# ledbrick_plus_led.net
KiCad netlist of a schematic drawn in Altium Designer
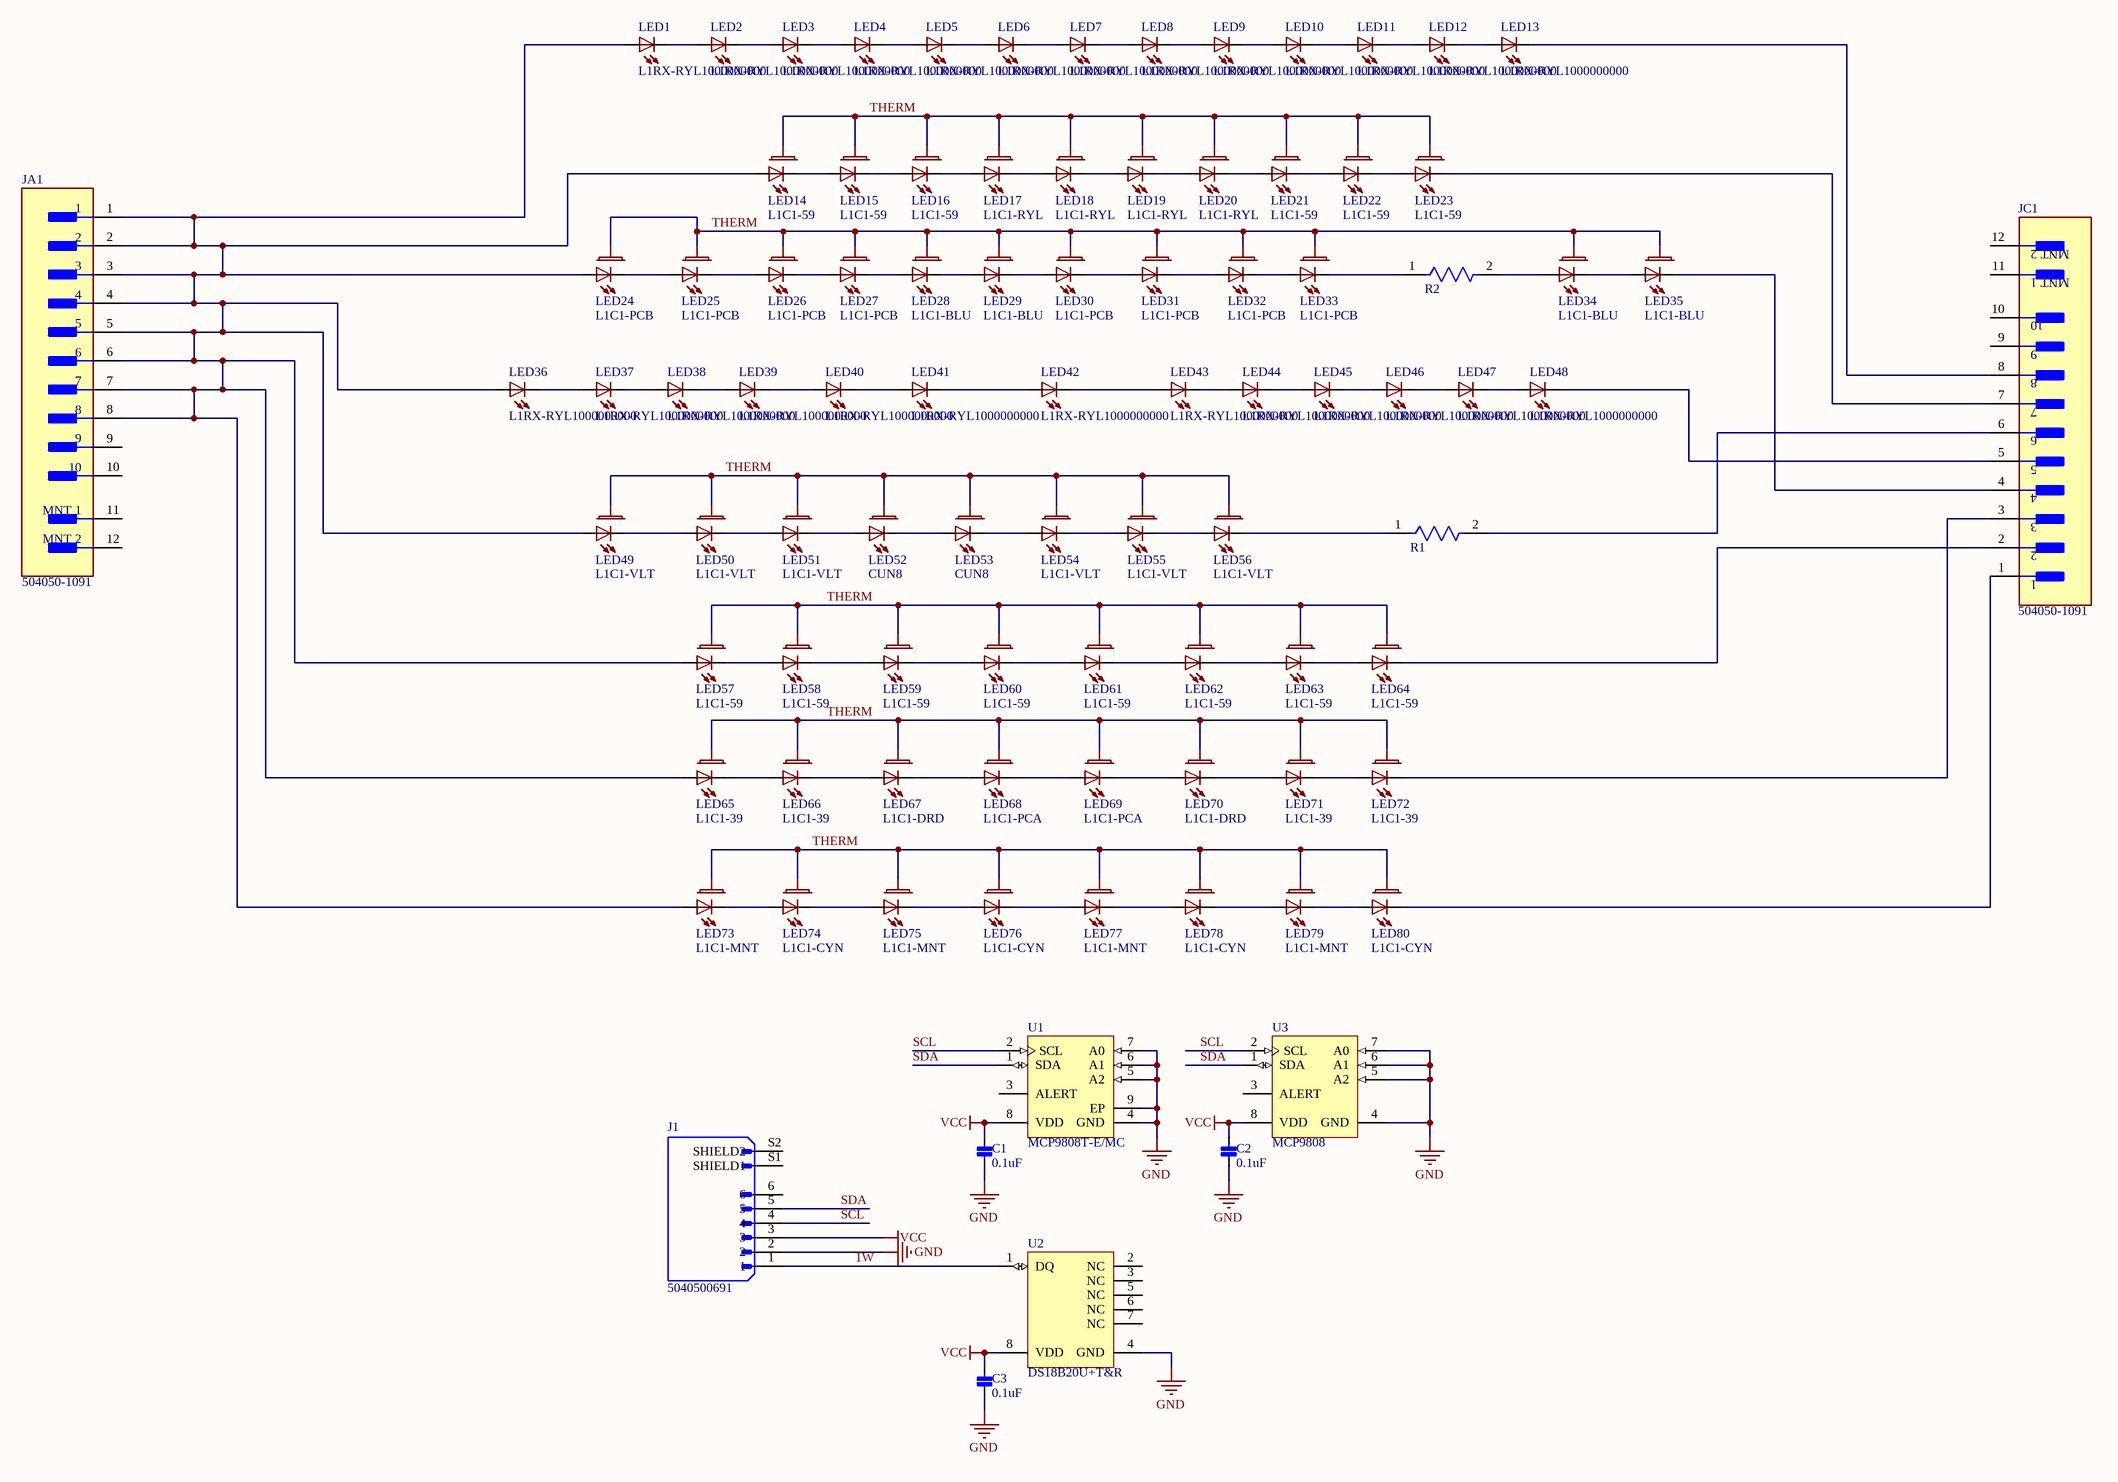
[diagram p0: ledbrick_plus_led.SchDoc]

(export (version "E")
  (design (tool "Eeschema 10.0.6"))
  (components
    (comp (ref "C1")
      (value "0.1uF")
      (footprint "FP-CL10-IPC_B")
      (description "Cap Ceramic 0.1uF 50V X7R 20% SMD 0603 125C Paper T/R")
      (fields (field (name "VOLTAGE") "50V") (field (name "Comment") "CAP 0.1uF 50V X7R 0603"))
      (libsource (lib "StackFoundry LLC") (part "C-EU"))
    )
    (comp (ref "C2")
      (value "0.1uF")
      (footprint "FP-CL10-IPC_B")
      (description "Cap Ceramic 0.1uF 50V X7R 20% SMD 0603 125C Paper T/R")
      (fields (field (name "VOLTAGE") "50V") (field (name "Comment") "CAP 0.1uF 50V X7R 0603"))
      (libsource (lib "StackFoundry LLC") (part "C-EU"))
    )
    (comp (ref "C3")
      (value "0.1uF")
      (footprint "FP-CL10-IPC_B")
      (description "Cap Ceramic 0.1uF 50V X7R 20% SMD 0603 125C Paper T/R")
      (fields (field (name "VOLTAGE") "50V") (field (name "Comment") "CAP 0.1uF 50V X7R 0603"))
      (libsource (lib "StackFoundry LLC") (part "C-EU"))
    )
    (comp (ref "J1")
      (value "5040500691")
      (footprint "MOLEX_5040500691")
      (description "CONN WIRE TO BOARD RA 6POS")
      (libsource (lib "StackFoundry LLC") (part "5040500691"))
    )
    (comp (ref "JA1")
      (value "504050-1091")
      (footprint "FP-504050-1091-MFG")
      (description "Conn Wire to Board HDR 10 POS 1.5mm Solder RA SMD Pico-Lock™ T/R")
      (libsource (lib "StackFoundry LLC") (part "6fa52caac0d1ee56d9e6a1d806c5b84"))
    )
    (comp (ref "JC1")
      (value "504050-1091")
      (footprint "FP-504050-1091-MFG")
      (description "Conn Wire to Board HDR 10 POS 1.5mm Solder RA SMD Pico-Lock™ T/R")
      (libsource (lib "") (part "6fa52caac0d1ee56d9e6a1d806c5b84_1"))
    )
    (comp (ref "LED1")
      (value "L1RX-RYL1000000000")
      (footprint "L1RX-RYL1000000000-Footprint-1")
      (description "LUXEON Rubix High Power LED Royal Blue Square Surface Mount 1635 lm 1.5 A 3.16 V")
      (libsource (lib "StackFoundry LLC") (part "L1RX-RYL"))
    )
    (comp (ref "LED2")
      (value "L1RX-RYL1000000000")
      (footprint "L1RX-RYL1000000000-Footprint-1")
      (description "LUXEON Rubix High Power LED Royal Blue Square Surface Mount 1635 lm 1.5 A 3.16 V")
      (libsource (lib "StackFoundry LLC") (part "L1RX-RYL"))
    )
    (comp (ref "LED3")
      (value "L1RX-RYL1000000000")
      (footprint "L1RX-RYL1000000000-Footprint-1")
      (description "LUXEON Rubix High Power LED Royal Blue Square Surface Mount 1635 lm 1.5 A 3.16 V")
      (libsource (lib "StackFoundry LLC") (part "L1RX-RYL"))
    )
    (comp (ref "LED4")
      (value "L1RX-RYL1000000000")
      (footprint "L1RX-RYL1000000000-Footprint-1")
      (description "LUXEON Rubix High Power LED Royal Blue Square Surface Mount 1635 lm 1.5 A 3.16 V")
      (libsource (lib "StackFoundry LLC") (part "L1RX-RYL"))
    )
    (comp (ref "LED5")
      (value "L1RX-RYL1000000000")
      (footprint "L1RX-RYL1000000000-Footprint-1")
      (description "LUXEON Rubix High Power LED Royal Blue Square Surface Mount 1635 lm 1.5 A 3.16 V")
      (libsource (lib "StackFoundry LLC") (part "L1RX-RYL"))
    )
    (comp (ref "LED6")
      (value "L1RX-RYL1000000000")
      (footprint "L1RX-RYL1000000000-Footprint-1")
      (description "LUXEON Rubix High Power LED Royal Blue Square Surface Mount 1635 lm 1.5 A 3.16 V")
      (libsource (lib "StackFoundry LLC") (part "L1RX-RYL"))
    )
    (comp (ref "LED7")
      (value "L1RX-RYL1000000000")
      (footprint "L1RX-RYL1000000000-Footprint-1")
      (description "LUXEON Rubix High Power LED Royal Blue Square Surface Mount 1635 lm 1.5 A 3.16 V")
      (libsource (lib "StackFoundry LLC") (part "L1RX-RYL"))
    )
    (comp (ref "LED8")
      (value "L1RX-RYL1000000000")
      (footprint "L1RX-RYL1000000000-Footprint-1")
      (description "LUXEON Rubix High Power LED Royal Blue Square Surface Mount 1635 lm 1.5 A 3.16 V")
      (libsource (lib "StackFoundry LLC") (part "L1RX-RYL"))
    )
    (comp (ref "LED9")
      (value "L1RX-RYL1000000000")
      (footprint "L1RX-RYL1000000000-Footprint-1")
      (description "LUXEON Rubix High Power LED Royal Blue Square Surface Mount 1635 lm 1.5 A 3.16 V")
      (libsource (lib "StackFoundry LLC") (part "L1RX-RYL"))
    )
    (comp (ref "LED10")
      (value "L1RX-RYL1000000000")
      (footprint "L1RX-RYL1000000000-Footprint-1")
      (description "LUXEON Rubix High Power LED Royal Blue Square Surface Mount 1635 lm 1.5 A 3.16 V")
      (libsource (lib "StackFoundry LLC") (part "L1RX-RYL"))
    )
    (comp (ref "LED11")
      (value "L1RX-RYL1000000000")
      (footprint "L1RX-RYL1000000000-Footprint-1")
      (description "LUXEON Rubix High Power LED Royal Blue Square Surface Mount 1635 lm 1.5 A 3.16 V")
      (libsource (lib "StackFoundry LLC") (part "L1RX-RYL"))
    )
    (comp (ref "LED12")
      (value "L1RX-RYL1000000000")
      (footprint "L1RX-RYL1000000000-Footprint-1")
      (description "LUXEON Rubix High Power LED Royal Blue Square Surface Mount 1635 lm 1.5 A 3.16 V")
      (libsource (lib "StackFoundry LLC") (part "L1RX-RYL"))
    )
    (comp (ref "LED13")
      (value "L1RX-RYL1000000000")
      (footprint "L1RX-RYL1000000000-Footprint-1")
      (description "LUXEON Rubix High Power LED Royal Blue Square Surface Mount 1635 lm 1.5 A 3.16 V")
      (libsource (lib "StackFoundry LLC") (part "L1RX-RYL"))
    )
    (comp (ref "LED14")
      (value "L1C1-59")
      (footprint "LUXEON_C_DATASHEET")
      (libsource (lib "StackFoundry LLC") (part "LED_THERMAL"))
    )
    (comp (ref "LED15")
      (value "L1C1-59")
      (footprint "LUXEON_C_DATASHEET")
      (libsource (lib "StackFoundry LLC") (part "LED_THERMAL"))
    )
    (comp (ref "LED16")
      (value "L1C1-59")
      (footprint "LUXEON_C_DATASHEET")
      (libsource (lib "StackFoundry LLC") (part "LED_THERMAL"))
    )
    (comp (ref "LED17")
      (value "L1C1-RYL")
      (footprint "LUXEON_C_DATASHEET")
      (libsource (lib "StackFoundry LLC") (part "LED_THERMAL"))
    )
    (comp (ref "LED18")
      (value "L1C1-RYL")
      (footprint "LUXEON_C_DATASHEET")
      (libsource (lib "StackFoundry LLC") (part "LED_THERMAL"))
    )
    (comp (ref "LED19")
      (value "L1C1-RYL")
      (footprint "LUXEON_C_DATASHEET")
      (libsource (lib "StackFoundry LLC") (part "LED_THERMAL"))
    )
    (comp (ref "LED20")
      (value "L1C1-RYL")
      (footprint "LUXEON_C_DATASHEET")
      (libsource (lib "StackFoundry LLC") (part "LED_THERMAL"))
    )
    (comp (ref "LED21")
      (value "L1C1-59")
      (footprint "LUXEON_C_DATASHEET")
      (libsource (lib "StackFoundry LLC") (part "LED_THERMAL"))
    )
    (comp (ref "LED22")
      (value "L1C1-59")
      (footprint "LUXEON_C_DATASHEET")
      (libsource (lib "StackFoundry LLC") (part "LED_THERMAL"))
    )
    (comp (ref "LED23")
      (value "L1C1-59")
      (footprint "LUXEON_C_DATASHEET")
      (libsource (lib "StackFoundry LLC") (part "LED_THERMAL"))
    )
    (comp (ref "LED24")
      (value "L1C1-PCB")
      (footprint "LUXEON_C_DATASHEET")
      (libsource (lib "StackFoundry LLC") (part "LED_THERMAL"))
    )
    (comp (ref "LED25")
      (value "L1C1-PCB")
      (footprint "LUXEON_C_DATASHEET")
      (libsource (lib "StackFoundry LLC") (part "LED_THERMAL"))
    )
    (comp (ref "LED26")
      (value "L1C1-PCB")
      (footprint "LUXEON_C_DATASHEET")
      (libsource (lib "StackFoundry LLC") (part "LED_THERMAL"))
    )
    (comp (ref "LED27")
      (value "L1C1-PCB")
      (footprint "LUXEON_C_DATASHEET")
      (libsource (lib "StackFoundry LLC") (part "LED_THERMAL"))
    )
    (comp (ref "LED28")
      (value "L1C1-BLU")
      (footprint "LUXEON_C_DATASHEET")
      (libsource (lib "StackFoundry LLC") (part "LED_THERMAL"))
    )
    (comp (ref "LED29")
      (value "L1C1-BLU")
      (footprint "LUXEON_C_DATASHEET")
      (libsource (lib "StackFoundry LLC") (part "LED_THERMAL"))
    )
    (comp (ref "LED30")
      (value "L1C1-PCB")
      (footprint "LUXEON_C_DATASHEET")
      (libsource (lib "StackFoundry LLC") (part "LED_THERMAL"))
    )
    (comp (ref "LED31")
      (value "L1C1-PCB")
      (footprint "LUXEON_C_DATASHEET")
      (libsource (lib "StackFoundry LLC") (part "LED_THERMAL"))
    )
    (comp (ref "LED32")
      (value "L1C1-PCB")
      (footprint "LUXEON_C_DATASHEET")
      (libsource (lib "StackFoundry LLC") (part "LED_THERMAL"))
    )
    (comp (ref "LED33")
      (value "L1C1-PCB")
      (footprint "LUXEON_C_DATASHEET")
      (libsource (lib "StackFoundry LLC") (part "LED_THERMAL"))
    )
    (comp (ref "LED34")
      (value "L1C1-BLU")
      (footprint "LUXEON_C_DATASHEET")
      (libsource (lib "StackFoundry LLC") (part "LED_THERMAL"))
    )
    (comp (ref "LED35")
      (value "L1C1-BLU")
      (footprint "LUXEON_C_DATASHEET")
      (libsource (lib "StackFoundry LLC") (part "LED_THERMAL"))
    )
    (comp (ref "LED36")
      (value "L1RX-RYL1000000000")
      (footprint "L1RX-RYL1000000000-Footprint-1")
      (description "LUXEON Rubix High Power LED Royal Blue Square Surface Mount 1635 lm 1.5 A 3.16 V")
      (libsource (lib "StackFoundry LLC") (part "L1RX-RYL"))
    )
    (comp (ref "LED37")
      (value "L1RX-RYL1000000000")
      (footprint "L1RX-RYL1000000000-Footprint-1")
      (description "LUXEON Rubix High Power LED Royal Blue Square Surface Mount 1635 lm 1.5 A 3.16 V")
      (libsource (lib "StackFoundry LLC") (part "L1RX-RYL"))
    )
    (comp (ref "LED38")
      (value "L1RX-RYL1000000000")
      (footprint "L1RX-RYL1000000000-Footprint-1")
      (description "LUXEON Rubix High Power LED Royal Blue Square Surface Mount 1635 lm 1.5 A 3.16 V")
      (libsource (lib "StackFoundry LLC") (part "L1RX-RYL"))
    )
    (comp (ref "LED39")
      (value "L1RX-RYL1000000000")
      (footprint "L1RX-RYL1000000000-Footprint-1")
      (description "LUXEON Rubix High Power LED Royal Blue Square Surface Mount 1635 lm 1.5 A 3.16 V")
      (libsource (lib "StackFoundry LLC") (part "L1RX-RYL"))
    )
    (comp (ref "LED40")
      (value "L1RX-RYL1000000000")
      (footprint "L1RX-RYL1000000000-Footprint-1")
      (description "LUXEON Rubix High Power LED Royal Blue Square Surface Mount 1635 lm 1.5 A 3.16 V")
      (libsource (lib "StackFoundry LLC") (part "L1RX-RYL"))
    )
    (comp (ref "LED41")
      (value "L1RX-RYL1000000000")
      (footprint "L1RX-RYL1000000000-Footprint-1")
      (description "LUXEON Rubix High Power LED Royal Blue Square Surface Mount 1635 lm 1.5 A 3.16 V")
      (libsource (lib "StackFoundry LLC") (part "L1RX-RYL"))
    )
    (comp (ref "LED42")
      (value "L1RX-RYL1000000000")
      (footprint "L1RX-RYL1000000000-Footprint-1")
      (description "LUXEON Rubix High Power LED Royal Blue Square Surface Mount 1635 lm 1.5 A 3.16 V")
      (libsource (lib "StackFoundry LLC") (part "L1RX-RYL"))
    )
    (comp (ref "LED43")
      (value "L1RX-RYL1000000000")
      (footprint "L1RX-RYL1000000000-Footprint-1")
      (description "LUXEON Rubix High Power LED Royal Blue Square Surface Mount 1635 lm 1.5 A 3.16 V")
      (libsource (lib "StackFoundry LLC") (part "L1RX-RYL"))
    )
    (comp (ref "LED44")
      (value "L1RX-RYL1000000000")
      (footprint "L1RX-RYL1000000000-Footprint-1")
      (description "LUXEON Rubix High Power LED Royal Blue Square Surface Mount 1635 lm 1.5 A 3.16 V")
      (libsource (lib "StackFoundry LLC") (part "L1RX-RYL"))
    )
    (comp (ref "LED45")
      (value "L1RX-RYL1000000000")
      (footprint "L1RX-RYL1000000000-Footprint-1")
      (description "LUXEON Rubix High Power LED Royal Blue Square Surface Mount 1635 lm 1.5 A 3.16 V")
      (libsource (lib "StackFoundry LLC") (part "L1RX-RYL"))
    )
    (comp (ref "LED46")
      (value "L1RX-RYL1000000000")
      (footprint "L1RX-RYL1000000000-Footprint-1")
      (description "LUXEON Rubix High Power LED Royal Blue Square Surface Mount 1635 lm 1.5 A 3.16 V")
      (libsource (lib "StackFoundry LLC") (part "L1RX-RYL"))
    )
    (comp (ref "LED47")
      (value "L1RX-RYL1000000000")
      (footprint "L1RX-RYL1000000000-Footprint-1")
      (description "LUXEON Rubix High Power LED Royal Blue Square Surface Mount 1635 lm 1.5 A 3.16 V")
      (libsource (lib "StackFoundry LLC") (part "L1RX-RYL"))
    )
    (comp (ref "LED48")
      (value "L1RX-RYL1000000000")
      (footprint "L1RX-RYL1000000000-Footprint-1")
      (description "LUXEON Rubix High Power LED Royal Blue Square Surface Mount 1635 lm 1.5 A 3.16 V")
      (libsource (lib "StackFoundry LLC") (part "L1RX-RYL"))
    )
    (comp (ref "LED49")
      (value "L1C1-VLT")
      (footprint "LUXEON_C_DATASHEET")
      (libsource (lib "StackFoundry LLC") (part "LED_THERMAL"))
    )
    (comp (ref "LED50")
      (value "L1C1-VLT")
      (footprint "LUXEON_C_DATASHEET")
      (libsource (lib "StackFoundry LLC") (part "LED_THERMAL"))
    )
    (comp (ref "LED51")
      (value "L1C1-VLT")
      (footprint "LUXEON_C_DATASHEET")
      (libsource (lib "StackFoundry LLC") (part "LED_THERMAL"))
    )
    (comp (ref "LED52")
      (value "CUN8")
      (footprint "VIOSYS_Z5")
      (libsource (lib "StackFoundry LLC") (part "LED_THERMAL"))
    )
    (comp (ref "LED53")
      (value "CUN8")
      (footprint "VIOSYS_Z5")
      (libsource (lib "StackFoundry LLC") (part "LED_THERMAL"))
    )
    (comp (ref "LED54")
      (value "L1C1-VLT")
      (footprint "LUXEON_C_DATASHEET")
      (libsource (lib "StackFoundry LLC") (part "LED_THERMAL"))
    )
    (comp (ref "LED55")
      (value "L1C1-VLT")
      (footprint "LUXEON_C_DATASHEET")
      (libsource (lib "StackFoundry LLC") (part "LED_THERMAL"))
    )
    (comp (ref "LED56")
      (value "L1C1-VLT")
      (footprint "LUXEON_C_DATASHEET")
      (libsource (lib "StackFoundry LLC") (part "LED_THERMAL"))
    )
    (comp (ref "LED57")
      (value "L1C1-59")
      (footprint "LUXEON_C_DATASHEET")
      (libsource (lib "StackFoundry LLC") (part "LED_THERMAL"))
    )
    (comp (ref "LED58")
      (value "L1C1-59")
      (footprint "LUXEON_C_DATASHEET")
      (libsource (lib "StackFoundry LLC") (part "LED_THERMAL"))
    )
    (comp (ref "LED59")
      (value "L1C1-59")
      (footprint "LUXEON_C_DATASHEET")
      (libsource (lib "StackFoundry LLC") (part "LED_THERMAL"))
    )
    (comp (ref "LED60")
      (value "L1C1-59")
      (footprint "LUXEON_C_DATASHEET")
      (libsource (lib "StackFoundry LLC") (part "LED_THERMAL"))
    )
    (comp (ref "LED61")
      (value "L1C1-59")
      (footprint "LUXEON_C_DATASHEET")
      (libsource (lib "StackFoundry LLC") (part "LED_THERMAL"))
    )
    (comp (ref "LED62")
      (value "L1C1-59")
      (footprint "LUXEON_C_DATASHEET")
      (libsource (lib "StackFoundry LLC") (part "LED_THERMAL"))
    )
    (comp (ref "LED63")
      (value "L1C1-59")
      (footprint "LUXEON_C_DATASHEET")
      (libsource (lib "StackFoundry LLC") (part "LED_THERMAL"))
    )
    (comp (ref "LED64")
      (value "L1C1-59")
      (footprint "LUXEON_C_DATASHEET")
      (libsource (lib "StackFoundry LLC") (part "LED_THERMAL"))
    )
    (comp (ref "LED65")
      (value "L1C1-39")
      (footprint "LUXEON_C_DATASHEET")
      (libsource (lib "StackFoundry LLC") (part "LED_THERMAL"))
    )
    (comp (ref "LED66")
      (value "L1C1-39")
      (footprint "LUXEON_C_DATASHEET")
      (libsource (lib "StackFoundry LLC") (part "LED_THERMAL"))
    )
    (comp (ref "LED67")
      (value "L1C1-DRD")
      (footprint "LUXEON_C_DATASHEET")
      (libsource (lib "StackFoundry LLC") (part "LED_THERMAL"))
    )
    (comp (ref "LED68")
      (value "L1C1-PCA")
      (footprint "LUXEON_C_DATASHEET")
      (libsource (lib "StackFoundry LLC") (part "LED_THERMAL"))
    )
    (comp (ref "LED69")
      (value "L1C1-PCA")
      (footprint "LUXEON_C_DATASHEET")
      (libsource (lib "StackFoundry LLC") (part "LED_THERMAL"))
    )
    (comp (ref "LED70")
      (value "L1C1-DRD")
      (footprint "LUXEON_C_DATASHEET")
      (libsource (lib "StackFoundry LLC") (part "LED_THERMAL"))
    )
    (comp (ref "LED71")
      (value "L1C1-39")
      (footprint "LUXEON_C_DATASHEET")
      (libsource (lib "StackFoundry LLC") (part "LED_THERMAL"))
    )
    (comp (ref "LED72")
      (value "L1C1-39")
      (footprint "LUXEON_C_DATASHEET")
      (libsource (lib "StackFoundry LLC") (part "LED_THERMAL"))
    )
    (comp (ref "LED73")
      (value "L1C1-MNT")
      (footprint "LUXEON_C_DATASHEET")
      (libsource (lib "StackFoundry LLC") (part "LED_THERMAL"))
    )
    (comp (ref "LED74")
      (value "L1C1-CYN")
      (footprint "LUXEON_C_DATASHEET")
      (libsource (lib "StackFoundry LLC") (part "LED_THERMAL"))
    )
    (comp (ref "LED75")
      (value "L1C1-MNT")
      (footprint "LUXEON_C_DATASHEET")
      (libsource (lib "StackFoundry LLC") (part "LED_THERMAL"))
    )
    (comp (ref "LED76")
      (value "L1C1-CYN")
      (footprint "LUXEON_C_DATASHEET")
      (libsource (lib "StackFoundry LLC") (part "LED_THERMAL"))
    )
    (comp (ref "LED77")
      (value "L1C1-MNT")
      (footprint "LUXEON_C_DATASHEET")
      (libsource (lib "StackFoundry LLC") (part "LED_THERMAL"))
    )
    (comp (ref "LED78")
      (value "L1C1-CYN")
      (footprint "LUXEON_C_DATASHEET")
      (libsource (lib "StackFoundry LLC") (part "LED_THERMAL"))
    )
    (comp (ref "LED79")
      (value "L1C1-MNT")
      (footprint "LUXEON_C_DATASHEET")
      (libsource (lib "StackFoundry LLC") (part "LED_THERMAL"))
    )
    (comp (ref "LED80")
      (value "L1C1-CYN")
      (footprint "LUXEON_C_DATASHEET")
      (libsource (lib "StackFoundry LLC") (part "LED_THERMAL"))
    )
    (comp (ref "R1")
      (value "0R 1206")
      (footprint "FP-RC1206-IPC_B")
      (description "Res Jumper Thick Film 1206 0 Ohm 5% 1/4W Molded SMD Paper T/R")
      (fields (field (name "TOLERANCE") "5%"))
      (libsource (lib "StackFoundry LLC") (part "1029c3af85768c4190bb7ad29bc67b5"))
    )
    (comp (ref "R2")
      (value "0R 1206")
      (footprint "FP-RC1206-IPC_B")
      (description "Res Jumper Thick Film 1206 0 Ohm 5% 1/4W Molded SMD Paper T/R")
      (fields (field (name "TOLERANCE") "5%"))
      (libsource (lib "StackFoundry LLC") (part "1029c3af85768c4190bb7ad29bc67b5"))
    )
    (comp (ref "U1")
      (value "MCP9808T-E/MC")
      (footprint "MCHP-DFN-MC8_V")
      (description "Temp Sensor Digital Serial (2-Wire, I2C) 8-Pin DFN EP T/R")
      (libsource (lib "StackFoundry LLC") (part "MCHP-MCP9808-DFN-8"))
    )
    (comp (ref "U2")
      (value "DS18B20U+T&R")
      (footprint "MAXM-U8+1_N")
      (description "Temp Sensor Digital Serial (1-Wire) 8-Pin uMAX T/R")
      (libsource (lib "StackFoundry LLC") (part "DS18B20-U8"))
    )
    (comp (ref "U3")
      (value "MCP9808")
      (footprint "MCHP-MSOP-MS8_M")
      (description "Temp Sensor Digital Serial (2-Wire, I2C) 8-Pin MSOP Tube")
      (libsource (lib "StackFoundry LLC") (part "MCHP-MCP9808-MSOP-8"))
    )
  )
  (nets
    (net (code "1") (name "/1W") (class "Default")
      (node (ref "J1") (pin "1") (pinfunction "1_1") (pintype "passive"))
      (node (ref "U2") (pin "1") (pinfunction "DQ_1") (pintype "bidirectional"))
    )
    (net (code "2") (name "/SCL") (class "Default")
      (node (ref "J1") (pin "4") (pinfunction "4_4") (pintype "passive"))
      (node (ref "U1") (pin "2") (pinfunction "SCL_2") (pintype "input"))
      (node (ref "U3") (pin "2") (pinfunction "SCL_2") (pintype "input"))
    )
    (net (code "3") (name "/SDA") (class "Default")
      (node (ref "J1") (pin "5") (pinfunction "5_5") (pintype "passive"))
      (node (ref "U1") (pin "1") (pinfunction "SDA_1") (pintype "bidirectional"))
      (node (ref "U3") (pin "1") (pinfunction "SDA_1") (pintype "bidirectional"))
    )
    (net (code "4") (name "/THERM") (class "Default")
      (node (ref "LED14") (pin "PAD") (pinfunction "PAD_PAD") (pintype "passive"))
      (node (ref "LED15") (pin "PAD") (pinfunction "PAD_PAD") (pintype "passive"))
      (node (ref "LED16") (pin "PAD") (pinfunction "PAD_PAD") (pintype "passive"))
      (node (ref "LED17") (pin "PAD") (pinfunction "PAD_PAD") (pintype "passive"))
      (node (ref "LED18") (pin "PAD") (pinfunction "PAD_PAD") (pintype "passive"))
      (node (ref "LED19") (pin "PAD") (pinfunction "PAD_PAD") (pintype "passive"))
      (node (ref "LED20") (pin "PAD") (pinfunction "PAD_PAD") (pintype "passive"))
      (node (ref "LED21") (pin "PAD") (pinfunction "PAD_PAD") (pintype "passive"))
      (node (ref "LED22") (pin "PAD") (pinfunction "PAD_PAD") (pintype "passive"))
      (node (ref "LED23") (pin "PAD") (pinfunction "PAD_PAD") (pintype "passive"))
      (node (ref "LED24") (pin "PAD") (pinfunction "PAD_PAD") (pintype "passive"))
      (node (ref "LED25") (pin "PAD") (pinfunction "PAD_PAD") (pintype "passive"))
      (node (ref "LED26") (pin "PAD") (pinfunction "PAD_PAD") (pintype "passive"))
      (node (ref "LED27") (pin "PAD") (pinfunction "PAD_PAD") (pintype "passive"))
      (node (ref "LED28") (pin "PAD") (pinfunction "PAD_PAD") (pintype "passive"))
      (node (ref "LED29") (pin "PAD") (pinfunction "PAD_PAD") (pintype "passive"))
      (node (ref "LED30") (pin "PAD") (pinfunction "PAD_PAD") (pintype "passive"))
      (node (ref "LED31") (pin "PAD") (pinfunction "PAD_PAD") (pintype "passive"))
      (node (ref "LED32") (pin "PAD") (pinfunction "PAD_PAD") (pintype "passive"))
      (node (ref "LED33") (pin "PAD") (pinfunction "PAD_PAD") (pintype "passive"))
      (node (ref "LED34") (pin "PAD") (pinfunction "PAD_PAD") (pintype "passive"))
      (node (ref "LED35") (pin "PAD") (pinfunction "PAD_PAD") (pintype "passive"))
      (node (ref "LED49") (pin "PAD") (pinfunction "PAD_PAD") (pintype "passive"))
      (node (ref "LED50") (pin "PAD") (pinfunction "PAD_PAD") (pintype "passive"))
      (node (ref "LED51") (pin "PAD") (pinfunction "PAD_PAD") (pintype "passive"))
      (node (ref "LED52") (pin "PAD") (pinfunction "PAD_PAD") (pintype "passive"))
      (node (ref "LED53") (pin "PAD") (pinfunction "PAD_PAD") (pintype "passive"))
      (node (ref "LED54") (pin "PAD") (pinfunction "PAD_PAD") (pintype "passive"))
      (node (ref "LED55") (pin "PAD") (pinfunction "PAD_PAD") (pintype "passive"))
      (node (ref "LED56") (pin "PAD") (pinfunction "PAD_PAD") (pintype "passive"))
      (node (ref "LED57") (pin "PAD") (pinfunction "PAD_PAD") (pintype "passive"))
      (node (ref "LED58") (pin "PAD") (pinfunction "PAD_PAD") (pintype "passive"))
      (node (ref "LED59") (pin "PAD") (pinfunction "PAD_PAD") (pintype "passive"))
      (node (ref "LED60") (pin "PAD") (pinfunction "PAD_PAD") (pintype "passive"))
      (node (ref "LED61") (pin "PAD") (pinfunction "PAD_PAD") (pintype "passive"))
      (node (ref "LED62") (pin "PAD") (pinfunction "PAD_PAD") (pintype "passive"))
      (node (ref "LED63") (pin "PAD") (pinfunction "PAD_PAD") (pintype "passive"))
      (node (ref "LED64") (pin "PAD") (pinfunction "PAD_PAD") (pintype "passive"))
      (node (ref "LED65") (pin "PAD") (pinfunction "PAD_PAD") (pintype "passive"))
      (node (ref "LED66") (pin "PAD") (pinfunction "PAD_PAD") (pintype "passive"))
      (node (ref "LED67") (pin "PAD") (pinfunction "PAD_PAD") (pintype "passive"))
      (node (ref "LED68") (pin "PAD") (pinfunction "PAD_PAD") (pintype "passive"))
      (node (ref "LED69") (pin "PAD") (pinfunction "PAD_PAD") (pintype "passive"))
      (node (ref "LED70") (pin "PAD") (pinfunction "PAD_PAD") (pintype "passive"))
      (node (ref "LED71") (pin "PAD") (pinfunction "PAD_PAD") (pintype "passive"))
      (node (ref "LED72") (pin "PAD") (pinfunction "PAD_PAD") (pintype "passive"))
      (node (ref "LED73") (pin "PAD") (pinfunction "PAD_PAD") (pintype "passive"))
      (node (ref "LED74") (pin "PAD") (pinfunction "PAD_PAD") (pintype "passive"))
      (node (ref "LED75") (pin "PAD") (pinfunction "PAD_PAD") (pintype "passive"))
      (node (ref "LED76") (pin "PAD") (pinfunction "PAD_PAD") (pintype "passive"))
      (node (ref "LED77") (pin "PAD") (pinfunction "PAD_PAD") (pintype "passive"))
      (node (ref "LED78") (pin "PAD") (pinfunction "PAD_PAD") (pintype "passive"))
      (node (ref "LED79") (pin "PAD") (pinfunction "PAD_PAD") (pintype "passive"))
      (node (ref "LED80") (pin "PAD") (pinfunction "PAD_PAD") (pintype "passive"))
    )
    (net (code "5") (name "GND") (class "Default")
      (node (ref "C1") (pin "2") (pinfunction "2_2") (pintype "passive"))
      (node (ref "C2") (pin "2") (pinfunction "2_2") (pintype "passive"))
      (node (ref "C3") (pin "2") (pinfunction "2_2") (pintype "passive"))
      (node (ref "J1") (pin "2") (pinfunction "2_2") (pintype "passive"))
      (node (ref "U1") (pin "4") (pinfunction "GND_4") (pintype "power_in"))
      (node (ref "U1") (pin "5") (pinfunction "A2_5") (pintype "input"))
      (node (ref "U1") (pin "6") (pinfunction "A1_6") (pintype "input"))
      (node (ref "U1") (pin "7") (pinfunction "A0_7") (pintype "input"))
      (node (ref "U1") (pin "9") (pinfunction "EP_9") (pintype "power_in"))
      (node (ref "U2") (pin "4") (pinfunction "GND_4") (pintype "power_in"))
      (node (ref "U3") (pin "4") (pinfunction "GND_4") (pintype "power_in"))
      (node (ref "U3") (pin "5") (pinfunction "A2_5") (pintype "input"))
      (node (ref "U3") (pin "6") (pinfunction "A1_6") (pintype "input"))
      (node (ref "U3") (pin "7") (pinfunction "A0_7") (pintype "input"))
    )
    (net (code "6") (name "Net-(JA1-Pad1)") (class "Default")
      (node (ref "JA1") (pin "1") (pinfunction "1_1") (pintype "passive"))
      (node (ref "JA1") (pin "2") (pinfunction "2_2") (pintype "passive"))
      (node (ref "JA1") (pin "3") (pinfunction "3_3") (pintype "passive"))
      (node (ref "JA1") (pin "4") (pinfunction "4_4") (pintype "passive"))
      (node (ref "JA1") (pin "5") (pinfunction "5_5") (pintype "passive"))
      (node (ref "JA1") (pin "6") (pinfunction "6_6") (pintype "passive"))
      (node (ref "JA1") (pin "7") (pinfunction "7_7") (pintype "passive"))
      (node (ref "JA1") (pin "8") (pinfunction "8_8") (pintype "passive"))
      (node (ref "LED1") (pin "A") (pinfunction "A_A") (pintype "passive"))
      (node (ref "LED14") (pin "A") (pinfunction "A_A") (pintype "passive"))
      (node (ref "LED24") (pin "A") (pinfunction "A_A") (pintype "passive"))
      (node (ref "LED36") (pin "A") (pinfunction "A_A") (pintype "passive"))
      (node (ref "LED49") (pin "A") (pinfunction "A_A") (pintype "passive"))
      (node (ref "LED57") (pin "A") (pinfunction "A_A") (pintype "passive"))
      (node (ref "LED65") (pin "A") (pinfunction "A_A") (pintype "passive"))
      (node (ref "LED73") (pin "A") (pinfunction "A_A") (pintype "passive"))
    )
    (net (code "7") (name "Net-(JC1-Pad1)") (class "Default")
      (node (ref "JC1") (pin "1") (pinfunction "1_1") (pintype "passive"))
      (node (ref "LED80") (pin "C") (pinfunction "C_C") (pintype "passive"))
    )
    (net (code "8") (name "Net-(JC1-Pad2)") (class "Default")
      (node (ref "JC1") (pin "2") (pinfunction "2_2") (pintype "passive"))
      (node (ref "LED64") (pin "C") (pinfunction "C_C") (pintype "passive"))
    )
    (net (code "9") (name "Net-(JC1-Pad3)") (class "Default")
      (node (ref "JC1") (pin "3") (pinfunction "3_3") (pintype "passive"))
      (node (ref "LED72") (pin "C") (pinfunction "C_C") (pintype "passive"))
    )
    (net (code "10") (name "Net-(JC1-Pad4)") (class "Default")
      (node (ref "JC1") (pin "4") (pinfunction "4_4") (pintype "passive"))
      (node (ref "LED35") (pin "C") (pinfunction "C_C") (pintype "passive"))
    )
    (net (code "11") (name "Net-(JC1-Pad5)") (class "Default")
      (node (ref "JC1") (pin "5") (pinfunction "5_5") (pintype "passive"))
      (node (ref "LED48") (pin "C") (pinfunction "C_C") (pintype "passive"))
    )
    (net (code "12") (name "Net-(JC1-Pad6)") (class "Default")
      (node (ref "JC1") (pin "6") (pinfunction "6_6") (pintype "passive"))
      (node (ref "R1") (pin "2") (pinfunction "2_2") (pintype "passive"))
    )
    (net (code "13") (name "Net-(JC1-Pad7)") (class "Default")
      (node (ref "JC1") (pin "7") (pinfunction "7_7") (pintype "passive"))
      (node (ref "LED23") (pin "C") (pinfunction "C_C") (pintype "passive"))
    )
    (net (code "14") (name "Net-(JC1-Pad8)") (class "Default")
      (node (ref "JC1") (pin "8") (pinfunction "8_8") (pintype "passive"))
      (node (ref "LED13") (pin "C") (pinfunction "C_C") (pintype "passive"))
    )
    (net (code "15") (name "Net-(LED1-PadC)") (class "Default")
      (node (ref "LED1") (pin "C") (pinfunction "C_C") (pintype "passive"))
      (node (ref "LED2") (pin "A") (pinfunction "A_A") (pintype "passive"))
    )
    (net (code "16") (name "Net-(LED2-PadC)") (class "Default")
      (node (ref "LED2") (pin "C") (pinfunction "C_C") (pintype "passive"))
      (node (ref "LED3") (pin "A") (pinfunction "A_A") (pintype "passive"))
    )
    (net (code "17") (name "Net-(LED3-PadC)") (class "Default")
      (node (ref "LED3") (pin "C") (pinfunction "C_C") (pintype "passive"))
      (node (ref "LED4") (pin "A") (pinfunction "A_A") (pintype "passive"))
    )
    (net (code "18") (name "Net-(LED4-PadC)") (class "Default")
      (node (ref "LED4") (pin "C") (pinfunction "C_C") (pintype "passive"))
      (node (ref "LED5") (pin "A") (pinfunction "A_A") (pintype "passive"))
    )
    (net (code "19") (name "Net-(LED5-PadC)") (class "Default")
      (node (ref "LED5") (pin "C") (pinfunction "C_C") (pintype "passive"))
      (node (ref "LED6") (pin "A") (pinfunction "A_A") (pintype "passive"))
    )
    (net (code "20") (name "Net-(LED6-PadC)") (class "Default")
      (node (ref "LED6") (pin "C") (pinfunction "C_C") (pintype "passive"))
      (node (ref "LED7") (pin "A") (pinfunction "A_A") (pintype "passive"))
    )
    (net (code "21") (name "Net-(LED7-PadC)") (class "Default")
      (node (ref "LED7") (pin "C") (pinfunction "C_C") (pintype "passive"))
      (node (ref "LED8") (pin "A") (pinfunction "A_A") (pintype "passive"))
    )
    (net (code "22") (name "Net-(LED8-PadC)") (class "Default")
      (node (ref "LED8") (pin "C") (pinfunction "C_C") (pintype "passive"))
      (node (ref "LED9") (pin "A") (pinfunction "A_A") (pintype "passive"))
    )
    (net (code "23") (name "Net-(LED10-PadA)") (class "Default")
      (node (ref "LED10") (pin "A") (pinfunction "A_A") (pintype "passive"))
      (node (ref "LED9") (pin "C") (pinfunction "C_C") (pintype "passive"))
    )
    (net (code "24") (name "Net-(LED10-PadC)") (class "Default")
      (node (ref "LED10") (pin "C") (pinfunction "C_C") (pintype "passive"))
      (node (ref "LED11") (pin "A") (pinfunction "A_A") (pintype "passive"))
    )
    (net (code "25") (name "Net-(LED11-PadC)") (class "Default")
      (node (ref "LED11") (pin "C") (pinfunction "C_C") (pintype "passive"))
      (node (ref "LED12") (pin "A") (pinfunction "A_A") (pintype "passive"))
    )
    (net (code "26") (name "Net-(LED12-PadC)") (class "Default")
      (node (ref "LED12") (pin "C") (pinfunction "C_C") (pintype "passive"))
      (node (ref "LED13") (pin "A") (pinfunction "A_A") (pintype "passive"))
    )
    (net (code "27") (name "Net-(LED14-PadC)") (class "Default")
      (node (ref "LED14") (pin "C") (pinfunction "C_C") (pintype "passive"))
      (node (ref "LED15") (pin "A") (pinfunction "A_A") (pintype "passive"))
    )
    (net (code "28") (name "Net-(LED15-PadC)") (class "Default")
      (node (ref "LED15") (pin "C") (pinfunction "C_C") (pintype "passive"))
      (node (ref "LED16") (pin "A") (pinfunction "A_A") (pintype "passive"))
    )
    (net (code "29") (name "Net-(LED16-PadC)") (class "Default")
      (node (ref "LED16") (pin "C") (pinfunction "C_C") (pintype "passive"))
      (node (ref "LED17") (pin "A") (pinfunction "A_A") (pintype "passive"))
    )
    (net (code "30") (name "Net-(LED17-PadC)") (class "Default")
      (node (ref "LED17") (pin "C") (pinfunction "C_C") (pintype "passive"))
      (node (ref "LED18") (pin "A") (pinfunction "A_A") (pintype "passive"))
    )
    (net (code "31") (name "Net-(LED18-PadC)") (class "Default")
      (node (ref "LED18") (pin "C") (pinfunction "C_C") (pintype "passive"))
      (node (ref "LED19") (pin "A") (pinfunction "A_A") (pintype "passive"))
    )
    (net (code "32") (name "Net-(LED19-PadC)") (class "Default")
      (node (ref "LED19") (pin "C") (pinfunction "C_C") (pintype "passive"))
      (node (ref "LED20") (pin "A") (pinfunction "A_A") (pintype "passive"))
    )
    (net (code "33") (name "Net-(LED20-PadC)") (class "Default")
      (node (ref "LED20") (pin "C") (pinfunction "C_C") (pintype "passive"))
      (node (ref "LED21") (pin "A") (pinfunction "A_A") (pintype "passive"))
    )
    (net (code "34") (name "Net-(LED21-PadC)") (class "Default")
      (node (ref "LED21") (pin "C") (pinfunction "C_C") (pintype "passive"))
      (node (ref "LED22") (pin "A") (pinfunction "A_A") (pintype "passive"))
    )
    (net (code "35") (name "Net-(LED22-PadC)") (class "Default")
      (node (ref "LED22") (pin "C") (pinfunction "C_C") (pintype "passive"))
      (node (ref "LED23") (pin "A") (pinfunction "A_A") (pintype "passive"))
    )
    (net (code "36") (name "Net-(LED24-PadC)") (class "Default")
      (node (ref "LED24") (pin "C") (pinfunction "C_C") (pintype "passive"))
      (node (ref "LED25") (pin "A") (pinfunction "A_A") (pintype "passive"))
    )
    (net (code "37") (name "Net-(LED25-PadC)") (class "Default")
      (node (ref "LED25") (pin "C") (pinfunction "C_C") (pintype "passive"))
      (node (ref "LED26") (pin "A") (pinfunction "A_A") (pintype "passive"))
    )
    (net (code "38") (name "Net-(LED26-PadC)") (class "Default")
      (node (ref "LED26") (pin "C") (pinfunction "C_C") (pintype "passive"))
      (node (ref "LED27") (pin "A") (pinfunction "A_A") (pintype "passive"))
    )
    (net (code "39") (name "Net-(LED27-PadC)") (class "Default")
      (node (ref "LED27") (pin "C") (pinfunction "C_C") (pintype "passive"))
      (node (ref "LED28") (pin "A") (pinfunction "A_A") (pintype "passive"))
    )
    (net (code "40") (name "Net-(LED28-PadC)") (class "Default")
      (node (ref "LED28") (pin "C") (pinfunction "C_C") (pintype "passive"))
      (node (ref "LED29") (pin "A") (pinfunction "A_A") (pintype "passive"))
    )
    (net (code "41") (name "Net-(LED29-PadC)") (class "Default")
      (node (ref "LED29") (pin "C") (pinfunction "C_C") (pintype "passive"))
      (node (ref "LED30") (pin "A") (pinfunction "A_A") (pintype "passive"))
    )
    (net (code "42") (name "Net-(LED30-PadC)") (class "Default")
      (node (ref "LED30") (pin "C") (pinfunction "C_C") (pintype "passive"))
      (node (ref "LED31") (pin "A") (pinfunction "A_A") (pintype "passive"))
    )
    (net (code "43") (name "Net-(LED31-PadC)") (class "Default")
      (node (ref "LED31") (pin "C") (pinfunction "C_C") (pintype "passive"))
      (node (ref "LED32") (pin "A") (pinfunction "A_A") (pintype "passive"))
    )
    (net (code "44") (name "Net-(LED32-PadC)") (class "Default")
      (node (ref "LED32") (pin "C") (pinfunction "C_C") (pintype "passive"))
      (node (ref "LED33") (pin "A") (pinfunction "A_A") (pintype "passive"))
    )
    (net (code "45") (name "Net-(LED33-PadC)") (class "Default")
      (node (ref "LED33") (pin "C") (pinfunction "C_C") (pintype "passive"))
      (node (ref "R2") (pin "1") (pinfunction "1_1") (pintype "passive"))
    )
    (net (code "46") (name "Net-(LED34-PadA)") (class "Default")
      (node (ref "LED34") (pin "A") (pinfunction "A_A") (pintype "passive"))
      (node (ref "R2") (pin "2") (pinfunction "2_2") (pintype "passive"))
    )
    (net (code "47") (name "Net-(LED34-PadC)") (class "Default")
      (node (ref "LED34") (pin "C") (pinfunction "C_C") (pintype "passive"))
      (node (ref "LED35") (pin "A") (pinfunction "A_A") (pintype "passive"))
    )
    (net (code "48") (name "Net-(LED36-PadC)") (class "Default")
      (node (ref "LED36") (pin "C") (pinfunction "C_C") (pintype "passive"))
      (node (ref "LED37") (pin "A") (pinfunction "A_A") (pintype "passive"))
    )
    (net (code "49") (name "Net-(LED37-PadC)") (class "Default")
      (node (ref "LED37") (pin "C") (pinfunction "C_C") (pintype "passive"))
      (node (ref "LED38") (pin "A") (pinfunction "A_A") (pintype "passive"))
    )
    (net (code "50") (name "Net-(LED38-PadC)") (class "Default")
      (node (ref "LED38") (pin "C") (pinfunction "C_C") (pintype "passive"))
      (node (ref "LED39") (pin "A") (pinfunction "A_A") (pintype "passive"))
    )
    (net (code "51") (name "Net-(LED39-PadC)") (class "Default")
      (node (ref "LED39") (pin "C") (pinfunction "C_C") (pintype "passive"))
      (node (ref "LED40") (pin "A") (pinfunction "A_A") (pintype "passive"))
    )
    (net (code "52") (name "Net-(LED40-PadC)") (class "Default")
      (node (ref "LED40") (pin "C") (pinfunction "C_C") (pintype "passive"))
      (node (ref "LED41") (pin "A") (pinfunction "A_A") (pintype "passive"))
    )
    (net (code "53") (name "Net-(LED41-PadC)") (class "Default")
      (node (ref "LED41") (pin "C") (pinfunction "C_C") (pintype "passive"))
      (node (ref "LED42") (pin "A") (pinfunction "A_A") (pintype "passive"))
    )
    (net (code "54") (name "Net-(LED42-PadC)") (class "Default")
      (node (ref "LED42") (pin "C") (pinfunction "C_C") (pintype "passive"))
      (node (ref "LED43") (pin "A") (pinfunction "A_A") (pintype "passive"))
    )
    (net (code "55") (name "Net-(LED43-PadC)") (class "Default")
      (node (ref "LED43") (pin "C") (pinfunction "C_C") (pintype "passive"))
      (node (ref "LED44") (pin "A") (pinfunction "A_A") (pintype "passive"))
    )
    (net (code "56") (name "Net-(LED44-PadC)") (class "Default")
      (node (ref "LED44") (pin "C") (pinfunction "C_C") (pintype "passive"))
      (node (ref "LED45") (pin "A") (pinfunction "A_A") (pintype "passive"))
    )
    (net (code "57") (name "Net-(LED45-PadC)") (class "Default")
      (node (ref "LED45") (pin "C") (pinfunction "C_C") (pintype "passive"))
      (node (ref "LED46") (pin "A") (pinfunction "A_A") (pintype "passive"))
    )
    (net (code "58") (name "Net-(LED46-PadC)") (class "Default")
      (node (ref "LED46") (pin "C") (pinfunction "C_C") (pintype "passive"))
      (node (ref "LED47") (pin "A") (pinfunction "A_A") (pintype "passive"))
    )
    (net (code "59") (name "Net-(LED47-PadC)") (class "Default")
      (node (ref "LED47") (pin "C") (pinfunction "C_C") (pintype "passive"))
      (node (ref "LED48") (pin "A") (pinfunction "A_A") (pintype "passive"))
    )
    (net (code "60") (name "Net-(LED49-PadC)") (class "Default")
      (node (ref "LED49") (pin "C") (pinfunction "C_C") (pintype "passive"))
      (node (ref "LED50") (pin "A") (pinfunction "A_A") (pintype "passive"))
    )
    (net (code "61") (name "Net-(LED50-PadC)") (class "Default")
      (node (ref "LED50") (pin "C") (pinfunction "C_C") (pintype "passive"))
      (node (ref "LED51") (pin "A") (pinfunction "A_A") (pintype "passive"))
    )
    (net (code "62") (name "Net-(LED51-PadC)") (class "Default")
      (node (ref "LED51") (pin "C") (pinfunction "C_C") (pintype "passive"))
      (node (ref "LED52") (pin "A") (pinfunction "A_A") (pintype "passive"))
    )
    (net (code "63") (name "Net-(LED52-PadC)") (class "Default")
      (node (ref "LED52") (pin "C") (pinfunction "C_C") (pintype "passive"))
      (node (ref "LED53") (pin "A") (pinfunction "A_A") (pintype "passive"))
    )
    (net (code "64") (name "Net-(LED53-PadC)") (class "Default")
      (node (ref "LED53") (pin "C") (pinfunction "C_C") (pintype "passive"))
      (node (ref "LED54") (pin "A") (pinfunction "A_A") (pintype "passive"))
    )
    (net (code "65") (name "Net-(LED54-PadC)") (class "Default")
      (node (ref "LED54") (pin "C") (pinfunction "C_C") (pintype "passive"))
      (node (ref "LED55") (pin "A") (pinfunction "A_A") (pintype "passive"))
    )
    (net (code "66") (name "Net-(LED55-PadC)") (class "Default")
      (node (ref "LED55") (pin "C") (pinfunction "C_C") (pintype "passive"))
      (node (ref "LED56") (pin "A") (pinfunction "A_A") (pintype "passive"))
    )
    (net (code "67") (name "Net-(LED56-PadC)") (class "Default")
      (node (ref "LED56") (pin "C") (pinfunction "C_C") (pintype "passive"))
      (node (ref "R1") (pin "1") (pinfunction "1_1") (pintype "passive"))
    )
    (net (code "68") (name "Net-(LED57-PadC)") (class "Default")
      (node (ref "LED57") (pin "C") (pinfunction "C_C") (pintype "passive"))
      (node (ref "LED58") (pin "A") (pinfunction "A_A") (pintype "passive"))
    )
    (net (code "69") (name "Net-(LED58-PadC)") (class "Default")
      (node (ref "LED58") (pin "C") (pinfunction "C_C") (pintype "passive"))
      (node (ref "LED59") (pin "A") (pinfunction "A_A") (pintype "passive"))
    )
    (net (code "70") (name "Net-(LED59-PadC)") (class "Default")
      (node (ref "LED59") (pin "C") (pinfunction "C_C") (pintype "passive"))
      (node (ref "LED60") (pin "A") (pinfunction "A_A") (pintype "passive"))
    )
    (net (code "71") (name "Net-(LED60-PadC)") (class "Default")
      (node (ref "LED60") (pin "C") (pinfunction "C_C") (pintype "passive"))
      (node (ref "LED61") (pin "A") (pinfunction "A_A") (pintype "passive"))
    )
    (net (code "72") (name "Net-(LED61-PadC)") (class "Default")
      (node (ref "LED61") (pin "C") (pinfunction "C_C") (pintype "passive"))
      (node (ref "LED62") (pin "A") (pinfunction "A_A") (pintype "passive"))
    )
    (net (code "73") (name "Net-(LED62-PadC)") (class "Default")
      (node (ref "LED62") (pin "C") (pinfunction "C_C") (pintype "passive"))
      (node (ref "LED63") (pin "A") (pinfunction "A_A") (pintype "passive"))
    )
    (net (code "74") (name "Net-(LED63-PadC)") (class "Default")
      (node (ref "LED63") (pin "C") (pinfunction "C_C") (pintype "passive"))
      (node (ref "LED64") (pin "A") (pinfunction "A_A") (pintype "passive"))
    )
    (net (code "75") (name "Net-(LED65-PadC)") (class "Default")
      (node (ref "LED65") (pin "C") (pinfunction "C_C") (pintype "passive"))
      (node (ref "LED66") (pin "A") (pinfunction "A_A") (pintype "passive"))
    )
    (net (code "76") (name "Net-(LED66-PadC)") (class "Default")
      (node (ref "LED66") (pin "C") (pinfunction "C_C") (pintype "passive"))
      (node (ref "LED67") (pin "A") (pinfunction "A_A") (pintype "passive"))
    )
    (net (code "77") (name "Net-(LED67-PadC)") (class "Default")
      (node (ref "LED67") (pin "C") (pinfunction "C_C") (pintype "passive"))
      (node (ref "LED68") (pin "A") (pinfunction "A_A") (pintype "passive"))
    )
    (net (code "78") (name "Net-(LED68-PadC)") (class "Default")
      (node (ref "LED68") (pin "C") (pinfunction "C_C") (pintype "passive"))
      (node (ref "LED69") (pin "A") (pinfunction "A_A") (pintype "passive"))
    )
    (net (code "79") (name "Net-(LED69-PadC)") (class "Default")
      (node (ref "LED69") (pin "C") (pinfunction "C_C") (pintype "passive"))
      (node (ref "LED70") (pin "A") (pinfunction "A_A") (pintype "passive"))
    )
    (net (code "80") (name "Net-(LED70-PadC)") (class "Default")
      (node (ref "LED70") (pin "C") (pinfunction "C_C") (pintype "passive"))
      (node (ref "LED71") (pin "A") (pinfunction "A_A") (pintype "passive"))
    )
    (net (code "81") (name "Net-(LED71-PadC)") (class "Default")
      (node (ref "LED71") (pin "C") (pinfunction "C_C") (pintype "passive"))
      (node (ref "LED72") (pin "A") (pinfunction "A_A") (pintype "passive"))
    )
    (net (code "82") (name "Net-(LED73-PadC)") (class "Default")
      (node (ref "LED73") (pin "C") (pinfunction "C_C") (pintype "passive"))
      (node (ref "LED74") (pin "A") (pinfunction "A_A") (pintype "passive"))
    )
    (net (code "83") (name "Net-(LED74-PadC)") (class "Default")
      (node (ref "LED74") (pin "C") (pinfunction "C_C") (pintype "passive"))
      (node (ref "LED75") (pin "A") (pinfunction "A_A") (pintype "passive"))
    )
    (net (code "84") (name "Net-(LED75-PadC)") (class "Default")
      (node (ref "LED75") (pin "C") (pinfunction "C_C") (pintype "passive"))
      (node (ref "LED76") (pin "A") (pinfunction "A_A") (pintype "passive"))
    )
    (net (code "85") (name "Net-(LED76-PadC)") (class "Default")
      (node (ref "LED76") (pin "C") (pinfunction "C_C") (pintype "passive"))
      (node (ref "LED77") (pin "A") (pinfunction "A_A") (pintype "passive"))
    )
    (net (code "86") (name "Net-(LED77-PadC)") (class "Default")
      (node (ref "LED77") (pin "C") (pinfunction "C_C") (pintype "passive"))
      (node (ref "LED78") (pin "A") (pinfunction "A_A") (pintype "passive"))
    )
    (net (code "87") (name "Net-(LED78-PadC)") (class "Default")
      (node (ref "LED78") (pin "C") (pinfunction "C_C") (pintype "passive"))
      (node (ref "LED79") (pin "A") (pinfunction "A_A") (pintype "passive"))
    )
    (net (code "88") (name "Net-(LED79-PadC)") (class "Default")
      (node (ref "LED79") (pin "C") (pinfunction "C_C") (pintype "passive"))
      (node (ref "LED80") (pin "A") (pinfunction "A_A") (pintype "passive"))
    )
    (net (code "89") (name "VCC") (class "Default")
      (node (ref "C1") (pin "1") (pinfunction "1_1") (pintype "passive"))
      (node (ref "C2") (pin "1") (pinfunction "1_1") (pintype "passive"))
      (node (ref "C3") (pin "1") (pinfunction "1_1") (pintype "passive"))
      (node (ref "J1") (pin "3") (pinfunction "3_3") (pintype "passive"))
      (node (ref "U1") (pin "8") (pinfunction "VDD_8") (pintype "power_in"))
      (node (ref "U2") (pin "8") (pinfunction "VDD_8") (pintype "power_in"))
      (node (ref "U3") (pin "8") (pinfunction "VDD_8") (pintype "power_in"))
    )
    (net (code "90") (name "unconnected-(J1-Pad6)") (class "Default")
      (node (ref "J1") (pin "6") (pinfunction "6_6") (pintype "passive"))
    )
    (net (code "91") (name "unconnected-(J1-SHIELD1-PadS1)") (class "Default")
      (node (ref "J1") (pin "S1") (pinfunction "SHIELD1_S1") (pintype "passive"))
    )
    (net (code "92") (name "unconnected-(J1-SHIELD2-PadS2)") (class "Default")
      (node (ref "J1") (pin "S2") (pinfunction "SHIELD2_S2") (pintype "passive"))
    )
    (net (code "93") (name "unconnected-(JA1-MNT_1-Pad11)") (class "Default")
      (node (ref "JA1") (pin "11") (pinfunction "MNT_1_11") (pintype "passive"))
    )
    (net (code "94") (name "unconnected-(JA1-MNT_2-Pad12)") (class "Default")
      (node (ref "JA1") (pin "12") (pinfunction "MNT_2_12") (pintype "passive"))
    )
    (net (code "95") (name "unconnected-(JA1-Pad9)") (class "Default")
      (node (ref "JA1") (pin "9") (pinfunction "9_9") (pintype "passive"))
    )
    (net (code "96") (name "unconnected-(JA1-Pad10)") (class "Default")
      (node (ref "JA1") (pin "10") (pinfunction "10_10") (pintype "passive"))
    )
    (net (code "97") (name "unconnected-(JC1-MNT_1-Pad11)") (class "Default")
      (node (ref "JC1") (pin "11") (pinfunction "MNT_1_11") (pintype "passive"))
    )
    (net (code "98") (name "unconnected-(JC1-MNT_2-Pad12)") (class "Default")
      (node (ref "JC1") (pin "12") (pinfunction "MNT_2_12") (pintype "passive"))
    )
    (net (code "99") (name "unconnected-(JC1-Pad9)") (class "Default")
      (node (ref "JC1") (pin "9") (pinfunction "9_9") (pintype "passive"))
    )
    (net (code "100") (name "unconnected-(JC1-Pad10)") (class "Default")
      (node (ref "JC1") (pin "10") (pinfunction "10_10") (pintype "passive"))
    )
    (net (code "101") (name "unconnected-(U1-ALERT-Pad3)") (class "Default")
      (node (ref "U1") (pin "3") (pinfunction "ALERT_3") (pintype "open_collector"))
    )
    (net (code "102") (name "unconnected-(U2-NC-Pad2)") (class "Default")
      (node (ref "U2") (pin "2") (pinfunction "NC_2") (pintype "passive"))
    )
    (net (code "103") (name "unconnected-(U2-NC-Pad3)") (class "Default")
      (node (ref "U2") (pin "3") (pinfunction "NC_3") (pintype "passive"))
    )
    (net (code "104") (name "unconnected-(U2-NC-Pad5)") (class "Default")
      (node (ref "U2") (pin "5") (pinfunction "NC_5") (pintype "passive"))
    )
    (net (code "105") (name "unconnected-(U2-NC-Pad6)") (class "Default")
      (node (ref "U2") (pin "6") (pinfunction "NC_6") (pintype "passive"))
    )
    (net (code "106") (name "unconnected-(U2-NC-Pad7)") (class "Default")
      (node (ref "U2") (pin "7") (pinfunction "NC_7") (pintype "passive"))
    )
    (net (code "107") (name "unconnected-(U3-ALERT-Pad3)") (class "Default")
      (node (ref "U3") (pin "3") (pinfunction "ALERT_3") (pintype "open_collector"))
    )
  )
)
